# espism.net
KiCad netlist of a schematic drawn in EAGLE
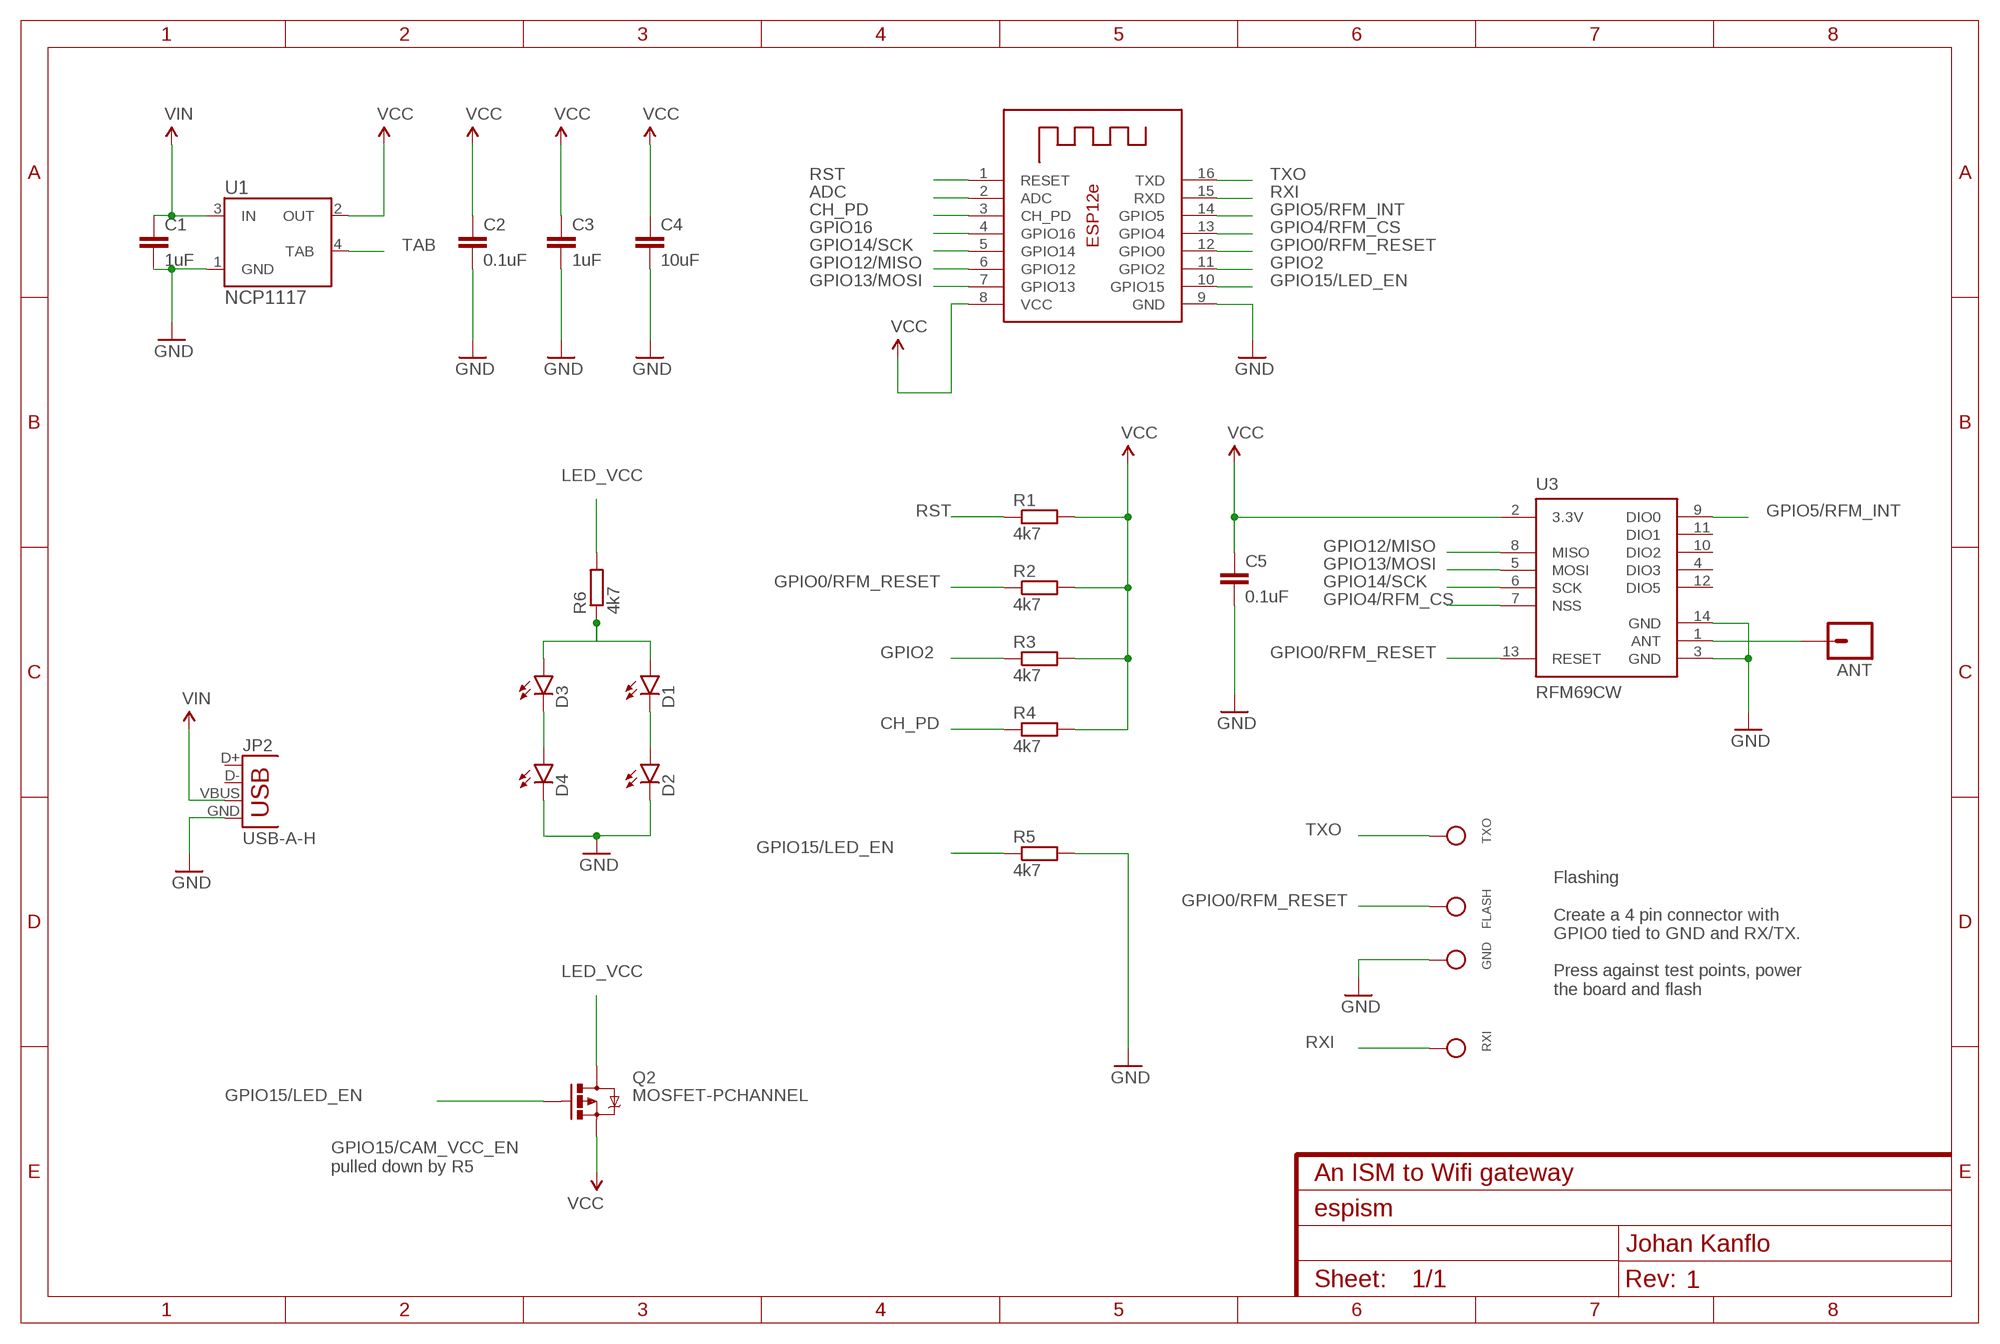
[diagram p0: schematic, sheet 1]

(export (version "E")
  (design (tool "Eeschema 10.0.6"))
  (components
    (comp (ref "ANT")
      (value "M01PTH")
      (footprint "eagle-import:1X01")
      (libsource (lib "eagle-import") (part "M01PTH"))
    )
    (comp (ref "C1")
      (value "1uF")
      (footprint "eagle-import:0603-CAP")
      (libsource (lib "eagle-import") (part "CAP0603-CAP"))
    )
    (comp (ref "C2")
      (value "0.1uF")
      (footprint "eagle-import:0603-CAP")
      (libsource (lib "eagle-import") (part "CAP0603-CAP"))
    )
    (comp (ref "C3")
      (value "1uF")
      (footprint "eagle-import:0603-CAP")
      (libsource (lib "eagle-import") (part "CAP0603-CAP"))
    )
    (comp (ref "C4")
      (value "10uF")
      (footprint "eagle-import:0603-CAP")
      (libsource (lib "eagle-import") (part "CAP0603-CAP"))
    )
    (comp (ref "C5")
      (value "0.1uF")
      (footprint "eagle-import:0603-CAP")
      (libsource (lib "eagle-import") (part "CAP0603-CAP"))
    )
    (comp (ref "D1")
      (value "LED0603")
      (footprint "eagle-import:LED-0603")
      (libsource (lib "eagle-import") (part "LED0603"))
    )
    (comp (ref "D2")
      (value "LED0603")
      (footprint "eagle-import:LED-0603")
      (libsource (lib "eagle-import") (part "LED0603"))
    )
    (comp (ref "D3")
      (value "LED0603")
      (footprint "eagle-import:LED-0603")
      (libsource (lib "eagle-import") (part "LED0603"))
    )
    (comp (ref "D4")
      (value "LED0603")
      (footprint "eagle-import:LED-0603")
      (libsource (lib "eagle-import") (part "LED0603"))
    )
    (comp (ref "FLASH")
      (value "TESTPOINTROUND1MM")
      (footprint "eagle-import:TESTPOINT_ROUND_1MM")
      (libsource (lib "eagle-import") (part "TESTPOINTROUND1MM"))
    )
    (comp (ref "GND")
      (value "TESTPOINTROUND1MM")
      (footprint "eagle-import:TESTPOINT_ROUND_1MM")
      (libsource (lib "eagle-import") (part "TESTPOINTROUND1MM"))
    )
    (comp (ref "JP2")
      (value "USB-A-H")
      (footprint "eagle-import:USB-A-H")
      (libsource (lib "eagle-import") (part "USB-A-H"))
    )
    (comp (ref "Q2")
      (value "MOSFET-PCHANNEL")
      (footprint "eagle-import:SOT23-3")
      (libsource (lib "eagle-import") (part "MOSFET-PCHANNEL"))
    )
    (comp (ref "R1")
      (value "4k7")
      (footprint "eagle-import:R0603")
      (libsource (lib "eagle-import") (part "R-EU_R0603"))
    )
    (comp (ref "R2")
      (value "4k7")
      (footprint "eagle-import:R0603")
      (libsource (lib "eagle-import") (part "R-EU_R0603"))
    )
    (comp (ref "R3")
      (value "4k7")
      (footprint "eagle-import:R0603")
      (libsource (lib "eagle-import") (part "R-EU_R0603"))
    )
    (comp (ref "R4")
      (value "4k7")
      (footprint "eagle-import:R0603")
      (libsource (lib "eagle-import") (part "R-EU_R0603"))
    )
    (comp (ref "R5")
      (value "4k7")
      (footprint "eagle-import:R0603")
      (libsource (lib "eagle-import") (part "R-EU_R0603"))
    )
    (comp (ref "R6")
      (value "4k7")
      (footprint "eagle-import:R0603")
      (libsource (lib "eagle-import") (part "R-EU_R0603"))
    )
    (comp (ref "RXI")
      (value "TESTPOINTROUND1MM")
      (footprint "eagle-import:TESTPOINT_ROUND_1MM")
      (libsource (lib "eagle-import") (part "TESTPOINTROUND1MM"))
    )
    (comp (ref "TXO")
      (value "TESTPOINTROUND1MM")
      (footprint "eagle-import:TESTPOINT_ROUND_1MM")
      (libsource (lib "eagle-import") (part "TESTPOINTROUND1MM"))
    )
    (comp (ref "U1")
      (value "NCP1117")
      (footprint "eagle-import:SOT223")
      (libsource (lib "eagle-import") (part "NCP1117"))
    )
    (comp (ref "U2")
      (value "ESP-12E")
      (footprint "eagle-import:ESP-12E")
      (libsource (lib "eagle-import") (part "ESP-12E"))
    )
    (comp (ref "U3")
      (value "RFM69CW")
      (footprint "eagle-import:RFM69CW-XXXS2")
      (libsource (lib "eagle-import") (part "RFM69CW"))
    )
  )
  (nets
    (net (code "1") (name "/ADC") (class "Default")
      (node (ref "U2") (pin "2") (pinfunction "ADC_2") (pintype "passive"))
    )
    (net (code "2") (name "/CH_PD") (class "Default")
      (node (ref "R4") (pin "1") (pinfunction "1_1") (pintype "passive"))
      (node (ref "U2") (pin "3") (pinfunction "CH_PD_3") (pintype "input"))
    )
    (net (code "3") (name "/GPIO0{slash}RFM_RESET") (class "Default")
      (node (ref "FLASH") (pin "P$1") (pinfunction "P$1_P$1") (pintype "bidirectional"))
      (node (ref "R2") (pin "1") (pinfunction "1_1") (pintype "passive"))
      (node (ref "U2") (pin "12") (pinfunction "GPIO0_12") (pintype "bidirectional"))
      (node (ref "U3") (pin "13") (pinfunction "RESET_13") (pintype "input"))
    )
    (net (code "4") (name "/GPIO2") (class "Default")
      (node (ref "R3") (pin "1") (pinfunction "1_1") (pintype "passive"))
      (node (ref "U2") (pin "11") (pinfunction "GPIO2_11") (pintype "bidirectional"))
    )
    (net (code "5") (name "/GPIO4{slash}RFM_CS") (class "Default")
      (node (ref "U2") (pin "13") (pinfunction "GPIO4_13") (pintype "bidirectional"))
      (node (ref "U3") (pin "7") (pinfunction "NSS_7") (pintype "input"))
    )
    (net (code "6") (name "/GPIO5{slash}RFM_INT") (class "Default")
      (node (ref "U2") (pin "14") (pinfunction "GPIO5_14") (pintype "bidirectional"))
      (node (ref "U3") (pin "9") (pinfunction "DIO0_9") (pintype "bidirectional"))
    )
    (net (code "7") (name "/GPIO12{slash}MISO") (class "Default")
      (node (ref "U2") (pin "6") (pinfunction "GPIO12_6") (pintype "bidirectional"))
      (node (ref "U3") (pin "8") (pinfunction "MISO_8") (pintype "bidirectional"))
    )
    (net (code "8") (name "/GPIO13{slash}MOSI") (class "Default")
      (node (ref "U2") (pin "7") (pinfunction "GPIO13_7") (pintype "bidirectional"))
      (node (ref "U3") (pin "5") (pinfunction "MOSI_5") (pintype "input"))
    )
    (net (code "9") (name "/GPIO14{slash}SCK") (class "Default")
      (node (ref "U2") (pin "5") (pinfunction "GPIO14_5") (pintype "bidirectional"))
      (node (ref "U3") (pin "6") (pinfunction "SCK_6") (pintype "input"))
    )
    (net (code "10") (name "/GPIO15{slash}LED_EN") (class "Default")
      (node (ref "Q2") (pin "1") (pinfunction "G_1") (pintype "passive"))
      (node (ref "R5") (pin "1") (pinfunction "1_1") (pintype "passive"))
      (node (ref "U2") (pin "10") (pinfunction "GPIO15_10") (pintype "bidirectional"))
    )
    (net (code "11") (name "/GPIO16") (class "Default")
      (node (ref "U2") (pin "4") (pinfunction "GPIO16_4") (pintype "bidirectional"))
    )
    (net (code "12") (name "/LED_VCC") (class "Default")
      (node (ref "Q2") (pin "3") (pinfunction "D_3") (pintype "passive"))
      (node (ref "R6") (pin "2") (pinfunction "2_2") (pintype "passive"))
    )
    (net (code "13") (name "/RST") (class "Default")
      (node (ref "R1") (pin "1") (pinfunction "1_1") (pintype "passive"))
      (node (ref "U2") (pin "1") (pinfunction "RESET_1") (pintype "input"))
    )
    (net (code "14") (name "/RXI") (class "Default")
      (node (ref "RXI") (pin "P$1") (pinfunction "P$1_P$1") (pintype "bidirectional"))
      (node (ref "U2") (pin "15") (pinfunction "RXD_15") (pintype "input"))
    )
    (net (code "15") (name "/TAB") (class "Default")
      (node (ref "U1") (pin "4") (pinfunction "TAB_4") (pintype "bidirectional"))
    )
    (net (code "16") (name "/TXO") (class "Default")
      (node (ref "TXO") (pin "P$1") (pinfunction "P$1_P$1") (pintype "bidirectional"))
      (node (ref "U2") (pin "16") (pinfunction "TXD_16") (pintype "output"))
    )
    (net (code "17") (name "GND") (class "Default")
      (node (ref "C1") (pin "2") (pinfunction "2_2") (pintype "passive"))
      (node (ref "C2") (pin "2") (pinfunction "2_2") (pintype "passive"))
      (node (ref "C3") (pin "2") (pinfunction "2_2") (pintype "passive"))
      (node (ref "C4") (pin "2") (pinfunction "2_2") (pintype "passive"))
      (node (ref "C5") (pin "2") (pinfunction "2_2") (pintype "passive"))
      (node (ref "D2") (pin "C") (pinfunction "C_C") (pintype "passive"))
      (node (ref "D4") (pin "C") (pinfunction "C_C") (pintype "passive"))
      (node (ref "GND") (pin "P$1") (pinfunction "P$1_P$1") (pintype "bidirectional"))
      (node (ref "JP2") (pin "GND") (pinfunction "GND_GND") (pintype "bidirectional"))
      (node (ref "R5") (pin "2") (pinfunction "2_2") (pintype "passive"))
      (node (ref "U1") (pin "1") (pinfunction "GND_1") (pintype "bidirectional"))
      (node (ref "U2") (pin "9") (pinfunction "GND_9") (pintype "power_in"))
      (node (ref "U3") (pin "14") (pinfunction "GND_14") (pintype "power_in"))
      (node (ref "U3") (pin "3") (pinfunction "GND_3") (pintype "power_in"))
    )
    (net (code "18") (name "Net-(D1-PadA)") (class "Default")
      (node (ref "D1") (pin "A") (pinfunction "A_A") (pintype "passive"))
      (node (ref "D3") (pin "A") (pinfunction "A_A") (pintype "passive"))
      (node (ref "R6") (pin "1") (pinfunction "1_1") (pintype "passive"))
    )
    (net (code "19") (name "Net-(D1-PadC)") (class "Default")
      (node (ref "D1") (pin "C") (pinfunction "C_C") (pintype "passive"))
      (node (ref "D2") (pin "A") (pinfunction "A_A") (pintype "passive"))
    )
    (net (code "20") (name "Net-(D3-PadC)") (class "Default")
      (node (ref "D3") (pin "C") (pinfunction "C_C") (pintype "passive"))
      (node (ref "D4") (pin "A") (pinfunction "A_A") (pintype "passive"))
    )
    (net (code "21") (name "Net-(U3-ANT)") (class "Default")
      (node (ref "ANT") (pin "1") (pinfunction "1_1") (pintype "passive"))
      (node (ref "U3") (pin "1") (pinfunction "ANT_1") (pintype "passive"))
    )
    (net (code "22") (name "VCC") (class "Default")
      (node (ref "C2") (pin "1") (pinfunction "1_1") (pintype "passive"))
      (node (ref "C3") (pin "1") (pinfunction "1_1") (pintype "passive"))
      (node (ref "C4") (pin "1") (pinfunction "1_1") (pintype "passive"))
      (node (ref "C5") (pin "1") (pinfunction "1_1") (pintype "passive"))
      (node (ref "Q2") (pin "2") (pinfunction "S_2") (pintype "passive"))
      (node (ref "R1") (pin "2") (pinfunction "2_2") (pintype "passive"))
      (node (ref "R2") (pin "2") (pinfunction "2_2") (pintype "passive"))
      (node (ref "R3") (pin "2") (pinfunction "2_2") (pintype "passive"))
      (node (ref "R4") (pin "2") (pinfunction "2_2") (pintype "passive"))
      (node (ref "U1") (pin "2") (pinfunction "OUT_2") (pintype "bidirectional"))
      (node (ref "U2") (pin "8") (pinfunction "VCC_8") (pintype "power_in"))
      (node (ref "U3") (pin "2") (pinfunction "3.3V_2") (pintype "power_in"))
    )
    (net (code "23") (name "VIN") (class "Default")
      (node (ref "C1") (pin "1") (pinfunction "1_1") (pintype "passive"))
      (node (ref "JP2") (pin "VBUS") (pinfunction "VBUS_VBUS") (pintype "bidirectional"))
      (node (ref "U1") (pin "3") (pinfunction "IN_3") (pintype "bidirectional"))
    )
    (net (code "24") (name "unconnected-(JP2-PadD+)") (class "Default")
      (node (ref "JP2") (pin "D+") (pinfunction "D+_D+") (pintype "bidirectional"))
    )
    (net (code "25") (name "unconnected-(JP2-PadD-)") (class "Default")
      (node (ref "JP2") (pin "D-") (pinfunction "D-_D-") (pintype "bidirectional"))
    )
    (net (code "26") (name "unconnected-(U3-DIO1-Pad11)") (class "Default")
      (node (ref "U3") (pin "11") (pinfunction "DIO1_11") (pintype "bidirectional"))
    )
    (net (code "27") (name "unconnected-(U3-DIO2-Pad10)") (class "Default")
      (node (ref "U3") (pin "10") (pinfunction "DIO2_10") (pintype "bidirectional"))
    )
    (net (code "28") (name "unconnected-(U3-DIO3-Pad4)") (class "Default")
      (node (ref "U3") (pin "4") (pinfunction "DIO3_4") (pintype "bidirectional"))
    )
    (net (code "29") (name "unconnected-(U3-DIO5-Pad12)") (class "Default")
      (node (ref "U3") (pin "12") (pinfunction "DIO5_12") (pintype "bidirectional"))
    )
  )
)
